# DebuggerConnectors.net
KiCad netlist of a schematic drawn in Altium Designer
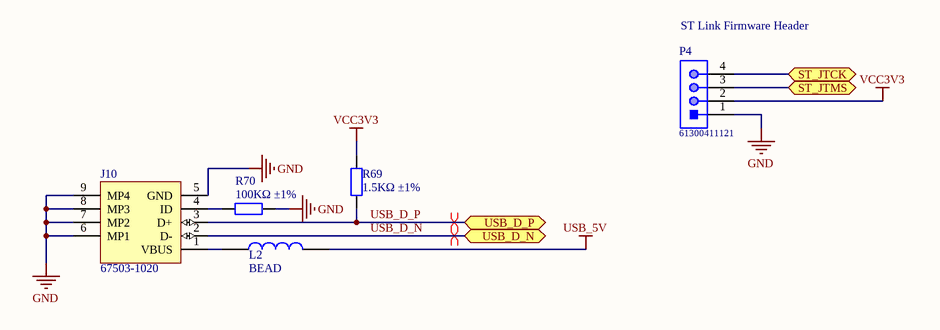
[diagram p0: DebuggerConnectors.SchDoc]

(export (version "E")
  (design (tool "Eeschema 10.0.6"))
  (components
    (comp (ref "J10")
      (value "67503-1020")
      (footprint "MOLX-67503-1020_V")
      (description "USB, MINI, SMD, RA KME04-USBMU03A01")
      (fields (field (name "MANUFACTURER") "Molex"))
      (libsource (lib "Altium Content Vault") (part "MOLX-67503-1020"))
    )
    (comp (ref "L2")
      (value "BEAD")
      (footprint "0603_L")
      (description "Ferrite Bead")
      (libsource (lib "FBEAD") (part "0603 100R@100Mhz 1A"))
    )
    (comp (ref "P4")
      (value "61300411121")
      (footprint "61300411121")
      (description "THT Vertical Pin Header WR-PHD, Pitch 2.54 mm, Single Row, 4 pins")
      (fields (field (name "MANUFACTURER") "Wurth Elektronik") (field (name "PUBLISHER") "WurthElektronik"))
      (libsource (lib "Altium Content Vault") (part "WE-CN-1P-M-R4"))
    )
    (comp (ref "R69")
      (value "1.5KΩ ±1%")
      (footprint "0402_R")
      (description "Chip resistor")
      (fields (field (name "MANUFACTURER") "Uniroyal Elec") (field (name "PARTNUMBER") "0402WGF1501TCE"))
      (libsource (lib "Miscellaneous Devices LC") (part "0402 1.5K (1501) 1%"))
    )
    (comp (ref "R70")
      (value "100KΩ ±1%")
      (footprint "0402_R")
      (description "Chip resistor")
      (fields (field (name "MANUFACTURER") "Uniroyal Elec") (field (name "PARTNUMBER") "0402WGF1003TCE"))
      (libsource (lib "Miscellaneous Devices LC") (part "0402 100K (1003) 1%"))
    )
  )
  (nets
    (net (code "1") (name "/ST_JTCK") (class "Default")
      (node (ref "P4") (pin "4") (pinfunction "4_4") (pintype "passive"))
    )
    (net (code "2") (name "/ST_JTMS") (class "Default")
      (node (ref "P4") (pin "3") (pinfunction "3_3") (pintype "passive"))
    )
    (net (code "3") (name "/USB_D_N") (class "Default")
      (node (ref "J10") (pin "2") (pinfunction "D-_2") (pintype "bidirectional"))
    )
    (net (code "4") (name "/USB_D_P") (class "Default")
      (node (ref "J10") (pin "3") (pinfunction "D+_3") (pintype "bidirectional"))
      (node (ref "R69") (pin "1") (pinfunction "1_1") (pintype "passive"))
    )
    (net (code "5") (name "GND") (class "Default")
      (node (ref "J10") (pin "5") (pinfunction "GND_5") (pintype "power_in"))
      (node (ref "J10") (pin "6") (pinfunction "MP1_6") (pintype "passive"))
      (node (ref "J10") (pin "7") (pinfunction "MP2_7") (pintype "passive"))
      (node (ref "J10") (pin "8") (pinfunction "MP3_8") (pintype "passive"))
      (node (ref "J10") (pin "9") (pinfunction "MP4_9") (pintype "passive"))
      (node (ref "P4") (pin "1") (pinfunction "1_1") (pintype "passive"))
      (node (ref "R70") (pin "2") (pinfunction "2_2") (pintype "passive"))
    )
    (net (code "6") (name "Net-(J10-ID)") (class "Default")
      (node (ref "J10") (pin "4") (pinfunction "ID_4") (pintype "passive"))
      (node (ref "R70") (pin "1") (pinfunction "1_1") (pintype "passive"))
    )
    (net (code "7") (name "Net-(J10-VBUS)") (class "Default")
      (node (ref "J10") (pin "1") (pinfunction "VBUS_1") (pintype "power_in"))
      (node (ref "L2") (pin "1") (pinfunction "1_1") (pintype "passive"))
    )
    (net (code "8") (name "USB_5V") (class "Default")
      (node (ref "L2") (pin "2") (pinfunction "2_2") (pintype "passive"))
    )
    (net (code "9") (name "VCC3V3") (class "Default")
      (node (ref "P4") (pin "2") (pinfunction "2_2") (pintype "passive"))
      (node (ref "R69") (pin "2") (pinfunction "2_2") (pintype "passive"))
    )
  )
)
